# CRUVI.net
KiCad netlist of a schematic drawn in Altium Designer
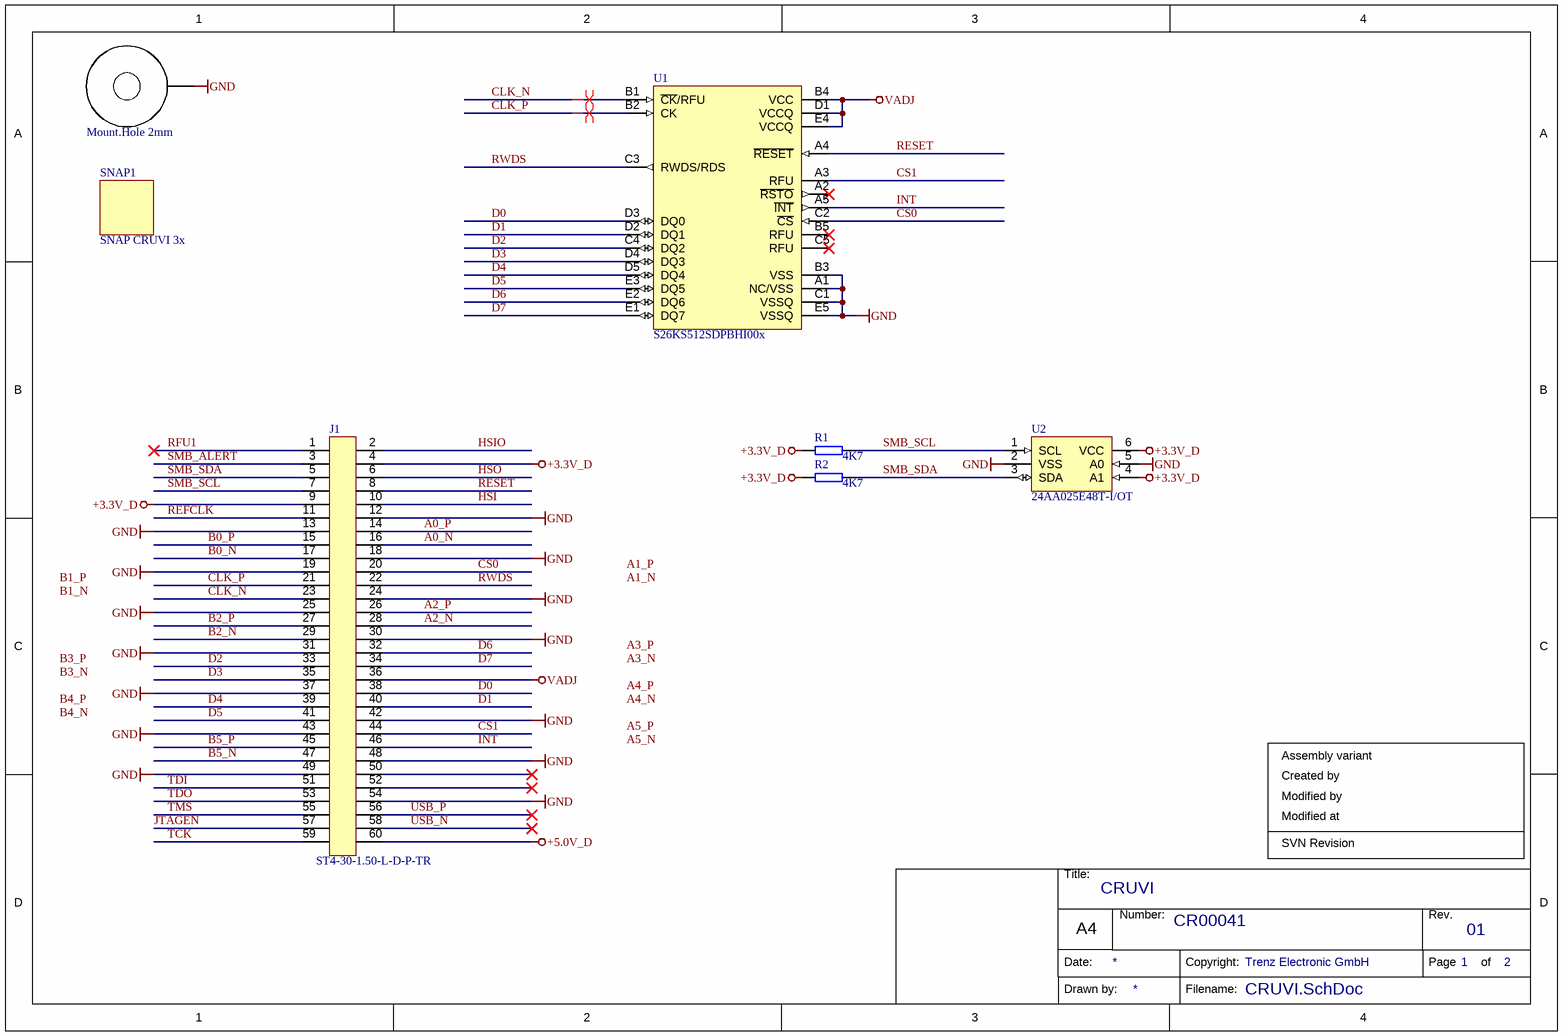
[diagram p0: CRUVI.SchDoc]

(export (version "E")
  (design (tool "Eeschema 10.0.6"))
  (components
    (comp (ref "H3") (value "Mount.Hole 2mm") (footprint "MHole2_2mm") (libsource (lib "TE") (part "MHole")))
    (comp (ref "J1")
      (value "ST4-30-1.50-L-D-P-TR")
      (footprint "ST4-30-1_50-L-D")
      (libsource (lib "TE") (part "CON-60"))
    )
    (comp (ref "R1")
      (value "4K7")
      (footprint "RESC1005X40N")
      (description "WID SMD 4K7 1% 0,063W BF 1005 (0402)")
      (fields (field (name "TOLERANCE") "1%"))
      (libsource (lib "TE") (part "RES"))
    )
    (comp (ref "R2")
      (value "4K7")
      (footprint "RESC1005X40N")
      (description "WID SMD 4K7 1% 0,063W BF 1005 (0402)")
      (fields (field (name "TOLERANCE") "1%"))
      (libsource (lib "TE") (part "RES"))
    )
    (comp (ref "SNAP1")
      (value "SNAP CRUVI 3x")
      (footprint "CRUVI_3x_Snap")
      (description "SNAP for CRUVI 3x")
      (libsource (lib "TE") (part "DUMMY"))
    )
    (comp (ref "U1")
      (value "S26KS512SDPBHI00x")
      (footprint "BGA25C100P5X5_800X600X120N")
      (description "S26KS512SDPBHI00x 1.8V")
      (libsource (lib "TE") (part "S26KS512S"))
    )
    (comp (ref "U2")
      (value "24AA025E48T-I/OT")
      (footprint "SOT95P280X145-6N")
      (libsource (lib "TE") (part "24AA025E48"))
    )
  )
  (nets
    (net (code "1") (name "+3.3V_D") (class "Default")
      (node (ref "J1") (pin "4") (pinfunction "4_4") (pintype "passive"))
      (node (ref "J1") (pin "9") (pinfunction "9_9") (pintype "passive"))
      (node (ref "R1") (pin "1") (pinfunction "1_1") (pintype "passive"))
      (node (ref "R2") (pin "1") (pinfunction "1_1") (pintype "passive"))
      (node (ref "U2") (pin "4") (pinfunction "A1_4") (pintype "input"))
      (node (ref "U2") (pin "6") (pinfunction "VCC_6") (pintype "power_in"))
    )
    (net (code "2") (name "+5.0V_D") (class "Default")
      (node (ref "J1") (pin "60") (pinfunction "60_60") (pintype "passive"))
    )
    (net (code "3") (name "/A0_N") (class "Default")
      (node (ref "J1") (pin "16") (pinfunction "16_16") (pintype "passive"))
    )
    (net (code "4") (name "/A0_P") (class "Default")
      (node (ref "J1") (pin "14") (pinfunction "14_14") (pintype "passive"))
    )
    (net (code "7") (name "/A2_N") (class "Default")
      (node (ref "J1") (pin "28") (pinfunction "28_28") (pintype "passive"))
    )
    (net (code "8") (name "/A2_P") (class "Default")
      (node (ref "J1") (pin "26") (pinfunction "26_26") (pintype "passive"))
    )
    (net (code "15") (name "/B0_N") (class "Default")
      (node (ref "J1") (pin "17") (pinfunction "17_17") (pintype "passive"))
    )
    (net (code "16") (name "/B0_P") (class "Default")
      (node (ref "J1") (pin "15") (pinfunction "15_15") (pintype "passive"))
    )
    (net (code "19") (name "/B2_N") (class "Default")
      (node (ref "J1") (pin "29") (pinfunction "29_29") (pintype "passive"))
    )
    (net (code "20") (name "/B2_P") (class "Default")
      (node (ref "J1") (pin "27") (pinfunction "27_27") (pintype "passive"))
    )
    (net (code "25") (name "/B5_N") (class "Default")
      (node (ref "J1") (pin "47") (pinfunction "47_47") (pintype "passive"))
    )
    (net (code "26") (name "/B5_P") (class "Default")
      (node (ref "J1") (pin "45") (pinfunction "45_45") (pintype "passive"))
    )
    (net (code "27") (name "/CLK_N") (class "Default")
      (node (ref "J1") (pin "23") (pinfunction "23_23") (pintype "passive"))
      (node (ref "U1") (pin "B1") (pinfunction "~{CK}/RFU_B1") (pintype "input"))
    )
    (net (code "28") (name "/CLK_P") (class "Default")
      (node (ref "J1") (pin "21") (pinfunction "21_21") (pintype "passive"))
      (node (ref "U1") (pin "B2") (pinfunction "CK_B2") (pintype "input"))
    )
    (net (code "29") (name "/CS0") (class "Default")
      (node (ref "J1") (pin "20") (pinfunction "20_20") (pintype "passive"))
      (node (ref "U1") (pin "C2") (pinfunction "~{CS}_C2") (pintype "input"))
    )
    (net (code "30") (name "/CS1") (class "Default")
      (node (ref "J1") (pin "44") (pinfunction "44_44") (pintype "passive"))
      (node (ref "U1") (pin "A3") (pinfunction "RFU_A3") (pintype "passive"))
    )
    (net (code "31") (name "/D0") (class "Default")
      (node (ref "J1") (pin "38") (pinfunction "38_38") (pintype "passive"))
      (node (ref "U1") (pin "D3") (pinfunction "DQ0_D3") (pintype "bidirectional"))
    )
    (net (code "32") (name "/D1") (class "Default")
      (node (ref "J1") (pin "40") (pinfunction "40_40") (pintype "passive"))
      (node (ref "U1") (pin "D2") (pinfunction "DQ1_D2") (pintype "bidirectional"))
    )
    (net (code "33") (name "/D2") (class "Default")
      (node (ref "J1") (pin "33") (pinfunction "33_33") (pintype "passive"))
      (node (ref "U1") (pin "C4") (pinfunction "DQ2_C4") (pintype "bidirectional"))
    )
    (net (code "34") (name "/D3") (class "Default")
      (node (ref "J1") (pin "35") (pinfunction "35_35") (pintype "passive"))
      (node (ref "U1") (pin "D4") (pinfunction "DQ3_D4") (pintype "bidirectional"))
    )
    (net (code "35") (name "/D4") (class "Default")
      (node (ref "J1") (pin "39") (pinfunction "39_39") (pintype "passive"))
      (node (ref "U1") (pin "D5") (pinfunction "DQ4_D5") (pintype "bidirectional"))
    )
    (net (code "36") (name "/D5") (class "Default")
      (node (ref "J1") (pin "41") (pinfunction "41_41") (pintype "passive"))
      (node (ref "U1") (pin "E3") (pinfunction "DQ5_E3") (pintype "bidirectional"))
    )
    (net (code "37") (name "/D6") (class "Default")
      (node (ref "J1") (pin "32") (pinfunction "32_32") (pintype "passive"))
      (node (ref "U1") (pin "E2") (pinfunction "DQ6_E2") (pintype "bidirectional"))
    )
    (net (code "38") (name "/D7") (class "Default")
      (node (ref "J1") (pin "34") (pinfunction "34_34") (pintype "passive"))
      (node (ref "U1") (pin "E1") (pinfunction "DQ7_E1") (pintype "bidirectional"))
    )
    (net (code "39") (name "/HSI") (class "Default")
      (node (ref "J1") (pin "10") (pinfunction "10_10") (pintype "passive"))
    )
    (net (code "40") (name "/HSIO") (class "Default")
      (node (ref "J1") (pin "2") (pinfunction "2_2") (pintype "passive"))
    )
    (net (code "41") (name "/HSO") (class "Default")
      (node (ref "J1") (pin "6") (pinfunction "6_6") (pintype "passive"))
    )
    (net (code "42") (name "/INT") (class "Default")
      (node (ref "J1") (pin "46") (pinfunction "46_46") (pintype "passive"))
      (node (ref "U1") (pin "A5") (pinfunction "~{INT}_A5") (pintype "output"))
    )
    (net (code "43") (name "/JTAGEN") (class "Default")
      (node (ref "J1") (pin "57") (pinfunction "57_57") (pintype "passive"))
    )
    (net (code "44") (name "/REFCLK") (class "Default")
      (node (ref "J1") (pin "11") (pinfunction "11_11") (pintype "passive"))
    )
    (net (code "45") (name "/RESET") (class "Default")
      (node (ref "J1") (pin "8") (pinfunction "8_8") (pintype "passive"))
      (node (ref "U1") (pin "A4") (pinfunction "~{RESET}_A4") (pintype "input"))
    )
    (net (code "46") (name "/RFU1") (class "Default")
      (node (ref "J1") (pin "1") (pinfunction "1_1") (pintype "passive+no_connect"))
    )
    (net (code "47") (name "/RWDS") (class "Default")
      (node (ref "J1") (pin "22") (pinfunction "22_22") (pintype "passive"))
      (node (ref "U1") (pin "C3") (pinfunction "RWDS/RDS_C3") (pintype "output"))
    )
    (net (code "48") (name "/SMB_ALERT") (class "Default")
      (node (ref "J1") (pin "3") (pinfunction "3_3") (pintype "passive"))
    )
    (net (code "49") (name "/SMB_SCL") (class "Default")
      (node (ref "J1") (pin "7") (pinfunction "7_7") (pintype "passive"))
      (node (ref "R1") (pin "2") (pinfunction "2_2") (pintype "passive"))
      (node (ref "U2") (pin "1") (pinfunction "SCL_1") (pintype "input"))
    )
    (net (code "50") (name "/SMB_SDA") (class "Default")
      (node (ref "J1") (pin "5") (pinfunction "5_5") (pintype "passive"))
      (node (ref "R2") (pin "2") (pinfunction "2_2") (pintype "passive"))
      (node (ref "U2") (pin "3") (pinfunction "SDA_3") (pintype "bidirectional"))
    )
    (net (code "51") (name "/TCK") (class "Default")
      (node (ref "J1") (pin "59") (pinfunction "59_59") (pintype "passive"))
    )
    (net (code "52") (name "/TDI") (class "Default")
      (node (ref "J1") (pin "51") (pinfunction "51_51") (pintype "passive"))
    )
    (net (code "53") (name "/TDO") (class "Default")
      (node (ref "J1") (pin "53") (pinfunction "53_53") (pintype "passive"))
    )
    (net (code "54") (name "/TMS") (class "Default")
      (node (ref "J1") (pin "55") (pinfunction "55_55") (pintype "passive"))
    )
    (net (code "55") (name "/USB_N") (class "Default")
      (node (ref "J1") (pin "58") (pinfunction "58_58") (pintype "passive+no_connect"))
    )
    (net (code "56") (name "/USB_P") (class "Default")
      (node (ref "J1") (pin "56") (pinfunction "56_56") (pintype "passive+no_connect"))
    )
    (net (code "57") (name "GND") (class "Default")
      (node (ref "H3") (pin "1") (pinfunction "1_1") (pintype "passive"))
      (node (ref "J1") (pin "12") (pinfunction "12_12") (pintype "passive"))
      (node (ref "J1") (pin "13") (pinfunction "13_13") (pintype "passive"))
      (node (ref "J1") (pin "18") (pinfunction "18_18") (pintype "passive"))
      (node (ref "J1") (pin "19") (pinfunction "19_19") (pintype "passive"))
      (node (ref "J1") (pin "24") (pinfunction "24_24") (pintype "passive"))
      (node (ref "J1") (pin "25") (pinfunction "25_25") (pintype "passive"))
      (node (ref "J1") (pin "30") (pinfunction "30_30") (pintype "passive"))
      (node (ref "J1") (pin "31") (pinfunction "31_31") (pintype "passive"))
      (node (ref "J1") (pin "37") (pinfunction "37_37") (pintype "passive"))
      (node (ref "J1") (pin "42") (pinfunction "42_42") (pintype "passive"))
      (node (ref "J1") (pin "43") (pinfunction "43_43") (pintype "passive"))
      (node (ref "J1") (pin "48") (pinfunction "48_48") (pintype "passive"))
      (node (ref "J1") (pin "49") (pinfunction "49_49") (pintype "passive"))
      (node (ref "J1") (pin "54") (pinfunction "54_54") (pintype "passive"))
      (node (ref "U1") (pin "A1") (pinfunction "NC/VSS_A1") (pintype "power_in"))
      (node (ref "U1") (pin "B3") (pinfunction "VSS_B3") (pintype "power_in"))
      (node (ref "U1") (pin "C1") (pinfunction "VSSQ_C1") (pintype "power_in"))
      (node (ref "U1") (pin "E5") (pinfunction "VSSQ_E5") (pintype "power_in"))
      (node (ref "U2") (pin "2") (pinfunction "VSS_2") (pintype "power_in"))
      (node (ref "U2") (pin "5") (pinfunction "A0_5") (pintype "input"))
    )
    (net (code "58") (name "VADJ") (class "Default")
      (node (ref "J1") (pin "36") (pinfunction "36_36") (pintype "passive"))
      (node (ref "U1") (pin "B4") (pinfunction "VCC_B4") (pintype "power_in"))
      (node (ref "U1") (pin "D1") (pinfunction "VCCQ_D1") (pintype "power_in"))
      (node (ref "U1") (pin "E4") (pinfunction "VCCQ_E4") (pintype "power_in"))
    )
    (net (code "59") (name "unconnected-(J1-Pad50)") (class "Default")
      (node (ref "J1") (pin "50") (pinfunction "50_50") (pintype "passive+no_connect"))
    )
    (net (code "60") (name "unconnected-(J1-Pad52)") (class "Default")
      (node (ref "J1") (pin "52") (pinfunction "52_52") (pintype "passive+no_connect"))
    )
    (net (code "61") (name "unconnected-(U1-RFU-PadB5)") (class "Default")
      (node (ref "U1") (pin "B5") (pinfunction "RFU_B5") (pintype "passive+no_connect"))
    )
    (net (code "62") (name "unconnected-(U1-RFU-PadC5)") (class "Default")
      (node (ref "U1") (pin "C5") (pinfunction "RFU_C5") (pintype "passive+no_connect"))
    )
    (net (code "63") (name "unconnected-(U1-~{RSTO}-PadA2)") (class "Default")
      (node (ref "U1") (pin "A2") (pinfunction "~{RSTO}_A2") (pintype "output+no_connect"))
    )
  )
)
